# Top.net
KiCad netlist of a schematic drawn in Altium Designer
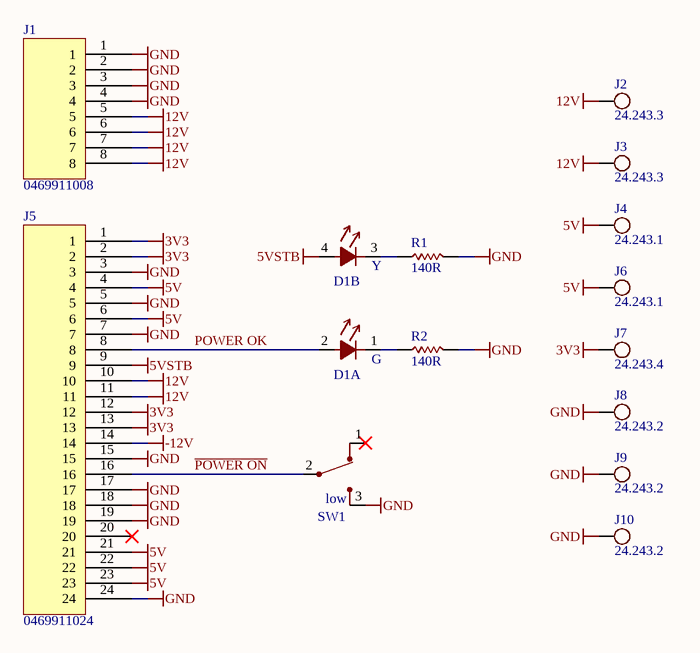
[diagram p0: Top.SchDoc]

(export (version "E")
  (design (tool "Eeschema 10.0.6"))
  (components
    (comp (ref "D1")
      (value "DUAL INDICATOR 5MM")
      (footprint "Dialight 552-0232F")
      (description "Dialight 552-0232F Indicator")
      (libsource (lib "PSSL3") (part "DUAL INDICATOR 5MM"))
    )
    (comp (ref "J1")
      (value "0469911008")
      (footprint "PCIE 8P POWER")
      (description "Molex MiniFit Jr 8 pin, PCIe power connector")
      (libsource (lib "PSSL3") (part "PCIE 8P"))
    )
    (comp (ref "J2")
      (value "24.243.3")
      (footprint "BANANA YL")
      (description "Banana jack, PCB mount right angle")
      (libsource (lib "PSSL3") (part "BANANA YELLOW"))
    )
    (comp (ref "J3")
      (value "24.243.3")
      (footprint "BANANA YL")
      (description "Banana jack, PCB mount right angle")
      (libsource (lib "PSSL3") (part "BANANA YELLOW"))
    )
    (comp (ref "J4")
      (value "24.243.1")
      (footprint "BANANA RD")
      (description "Banana jack, PCB mount right angle")
      (libsource (lib "PSSL3") (part "BANANA RED"))
    )
    (comp (ref "J5")
      (value "0469911024")
      (footprint "ATX 24P POWER")
      (description "Molex MiniFit Jr 24 pin, ATX power connector")
      (libsource (lib "PSSL3") (part "ATX 24P"))
    )
    (comp (ref "J6")
      (value "24.243.1")
      (footprint "BANANA RD")
      (description "Banana jack, PCB mount right angle")
      (libsource (lib "PSSL3") (part "BANANA RED"))
    )
    (comp (ref "J7")
      (value "24.243.4")
      (footprint "BANANA GR")
      (description "Banana jack, PCB mount right angle")
      (libsource (lib "PSSL3") (part "BANANA GREEN"))
    )
    (comp (ref "J8")
      (value "24.243.2")
      (footprint "BANANA BK")
      (description "Banana jack, PCB mount right angle")
      (libsource (lib "PSSL3") (part "BANANA BLACK"))
    )
    (comp (ref "J9")
      (value "24.243.2")
      (footprint "BANANA BK")
      (description "Banana jack, PCB mount right angle")
      (libsource (lib "PSSL3") (part "BANANA BLACK"))
    )
    (comp (ref "J10")
      (value "24.243.2")
      (footprint "BANANA BK")
      (description "Banana jack, PCB mount right angle")
      (libsource (lib "PSSL3") (part "BANANA BLACK"))
    )
    (comp (ref "R1")
      (value "140R")
      (footprint "0805")
      (description "805 Resistor")
      (libsource (lib "PSSL3") (part "RES 0805"))
    )
    (comp (ref "R2")
      (value "140R")
      (footprint "0805")
      (description "805 Resistor")
      (libsource (lib "PSSL3") (part "RES 0805"))
    )
    (comp (ref "SW1")
      (value "SWITCH")
      (footprint "7101SD9AV2BE")
      (description "Right-Angle Toogle Switch")
      (libsource (lib "PSSL3") (part "SWITCH"))
    )
  )
  (nets
    (net (code "1") (name "-12V") (class "Default")
      (node (ref "J5") (pin "14") (pinfunction "14_14") (pintype "power_in"))
    )
    (net (code "2") (name "/POWER OK") (class "Default")
      (node (ref "D1") (pin "2") (pintype "passive"))
      (node (ref "J5") (pin "8") (pinfunction "8_8") (pintype "power_in"))
    )
    (net (code "3") (name "/~{POWER ON}") (class "Default")
      (node (ref "J5") (pin "16") (pinfunction "16_16") (pintype "power_in"))
      (node (ref "SW1") (pin "2") (pintype "passive"))
    )
    (net (code "4") (name "3V3") (class "Default")
      (node (ref "J5") (pin "1") (pinfunction "1_1") (pintype "power_in"))
      (node (ref "J5") (pin "12") (pinfunction "12_12") (pintype "power_in"))
      (node (ref "J5") (pin "13") (pinfunction "13_13") (pintype "power_in"))
      (node (ref "J5") (pin "2") (pinfunction "2_2") (pintype "power_in"))
      (node (ref "J7") (pin "1") (pinfunction "TP_1") (pintype "passive"))
    )
    (net (code "5") (name "5V") (class "Default")
      (node (ref "J4") (pin "1") (pinfunction "TP_1") (pintype "passive"))
      (node (ref "J5") (pin "21") (pinfunction "21_21") (pintype "power_in"))
      (node (ref "J5") (pin "22") (pinfunction "22_22") (pintype "power_in"))
      (node (ref "J5") (pin "23") (pinfunction "23_23") (pintype "power_in"))
      (node (ref "J5") (pin "4") (pinfunction "4_4") (pintype "power_in"))
      (node (ref "J5") (pin "6") (pinfunction "6_6") (pintype "power_in"))
      (node (ref "J6") (pin "1") (pinfunction "TP_1") (pintype "passive"))
    )
    (net (code "6") (name "5VSTB") (class "Default")
      (node (ref "D1") (pin "4") (pintype "passive"))
      (node (ref "J5") (pin "9") (pinfunction "9_9") (pintype "power_in"))
    )
    (net (code "7") (name "12V") (class "Default")
      (node (ref "J1") (pin "5") (pinfunction "5_5") (pintype "power_in"))
      (node (ref "J1") (pin "6") (pinfunction "6_6") (pintype "power_in"))
      (node (ref "J1") (pin "7") (pinfunction "7_7") (pintype "power_in"))
      (node (ref "J1") (pin "8") (pinfunction "8_8") (pintype "power_in"))
      (node (ref "J2") (pin "1") (pinfunction "TP_1") (pintype "passive"))
      (node (ref "J3") (pin "1") (pinfunction "TP_1") (pintype "passive"))
      (node (ref "J5") (pin "10") (pinfunction "10_10") (pintype "power_in"))
      (node (ref "J5") (pin "11") (pinfunction "11_11") (pintype "power_in"))
    )
    (net (code "8") (name "GND") (class "Default")
      (node (ref "J1") (pin "1") (pinfunction "1_1") (pintype "power_in"))
      (node (ref "J1") (pin "2") (pinfunction "2_2") (pintype "power_in"))
      (node (ref "J1") (pin "3") (pinfunction "3_3") (pintype "power_in"))
      (node (ref "J1") (pin "4") (pinfunction "4_4") (pintype "power_in"))
      (node (ref "J10") (pin "1") (pinfunction "TP_1") (pintype "passive"))
      (node (ref "J5") (pin "15") (pinfunction "15_15") (pintype "power_in"))
      (node (ref "J5") (pin "17") (pinfunction "17_17") (pintype "power_in"))
      (node (ref "J5") (pin "18") (pinfunction "18_18") (pintype "power_in"))
      (node (ref "J5") (pin "19") (pinfunction "19_19") (pintype "power_in"))
      (node (ref "J5") (pin "24") (pinfunction "24_24") (pintype "power_in"))
      (node (ref "J5") (pin "3") (pinfunction "3_3") (pintype "power_in"))
      (node (ref "J5") (pin "5") (pinfunction "5_5") (pintype "power_in"))
      (node (ref "J5") (pin "7") (pinfunction "7_7") (pintype "power_in"))
      (node (ref "J8") (pin "1") (pinfunction "TP_1") (pintype "passive"))
      (node (ref "J9") (pin "1") (pinfunction "TP_1") (pintype "passive"))
      (node (ref "R1") (pin "1") (pintype "passive"))
      (node (ref "R2") (pin "1") (pintype "passive"))
      (node (ref "SW1") (pin "3") (pintype "passive"))
    )
    (net (code "9") (name "Net-(D1-Pad1)") (class "Default")
      (node (ref "D1") (pin "1") (pintype "passive"))
      (node (ref "R2") (pin "2") (pintype "passive"))
    )
    (net (code "10") (name "Net-(D1-Pad3)") (class "Default")
      (node (ref "D1") (pin "3") (pintype "passive"))
      (node (ref "R1") (pin "2") (pintype "passive"))
    )
    (net (code "11") (name "unconnected-(J5-Pad20)") (class "Default")
      (node (ref "J5") (pin "20") (pinfunction "20_20") (pintype "power_in+no_connect"))
    )
    (net (code "12") (name "unconnected-(SW1-Pad1)") (class "Default")
      (node (ref "SW1") (pin "1") (pintype "passive+no_connect"))
    )
  )
)
